# Toilet_Timer.net
KiCad netlist of a schematic drawn in Altium Designer
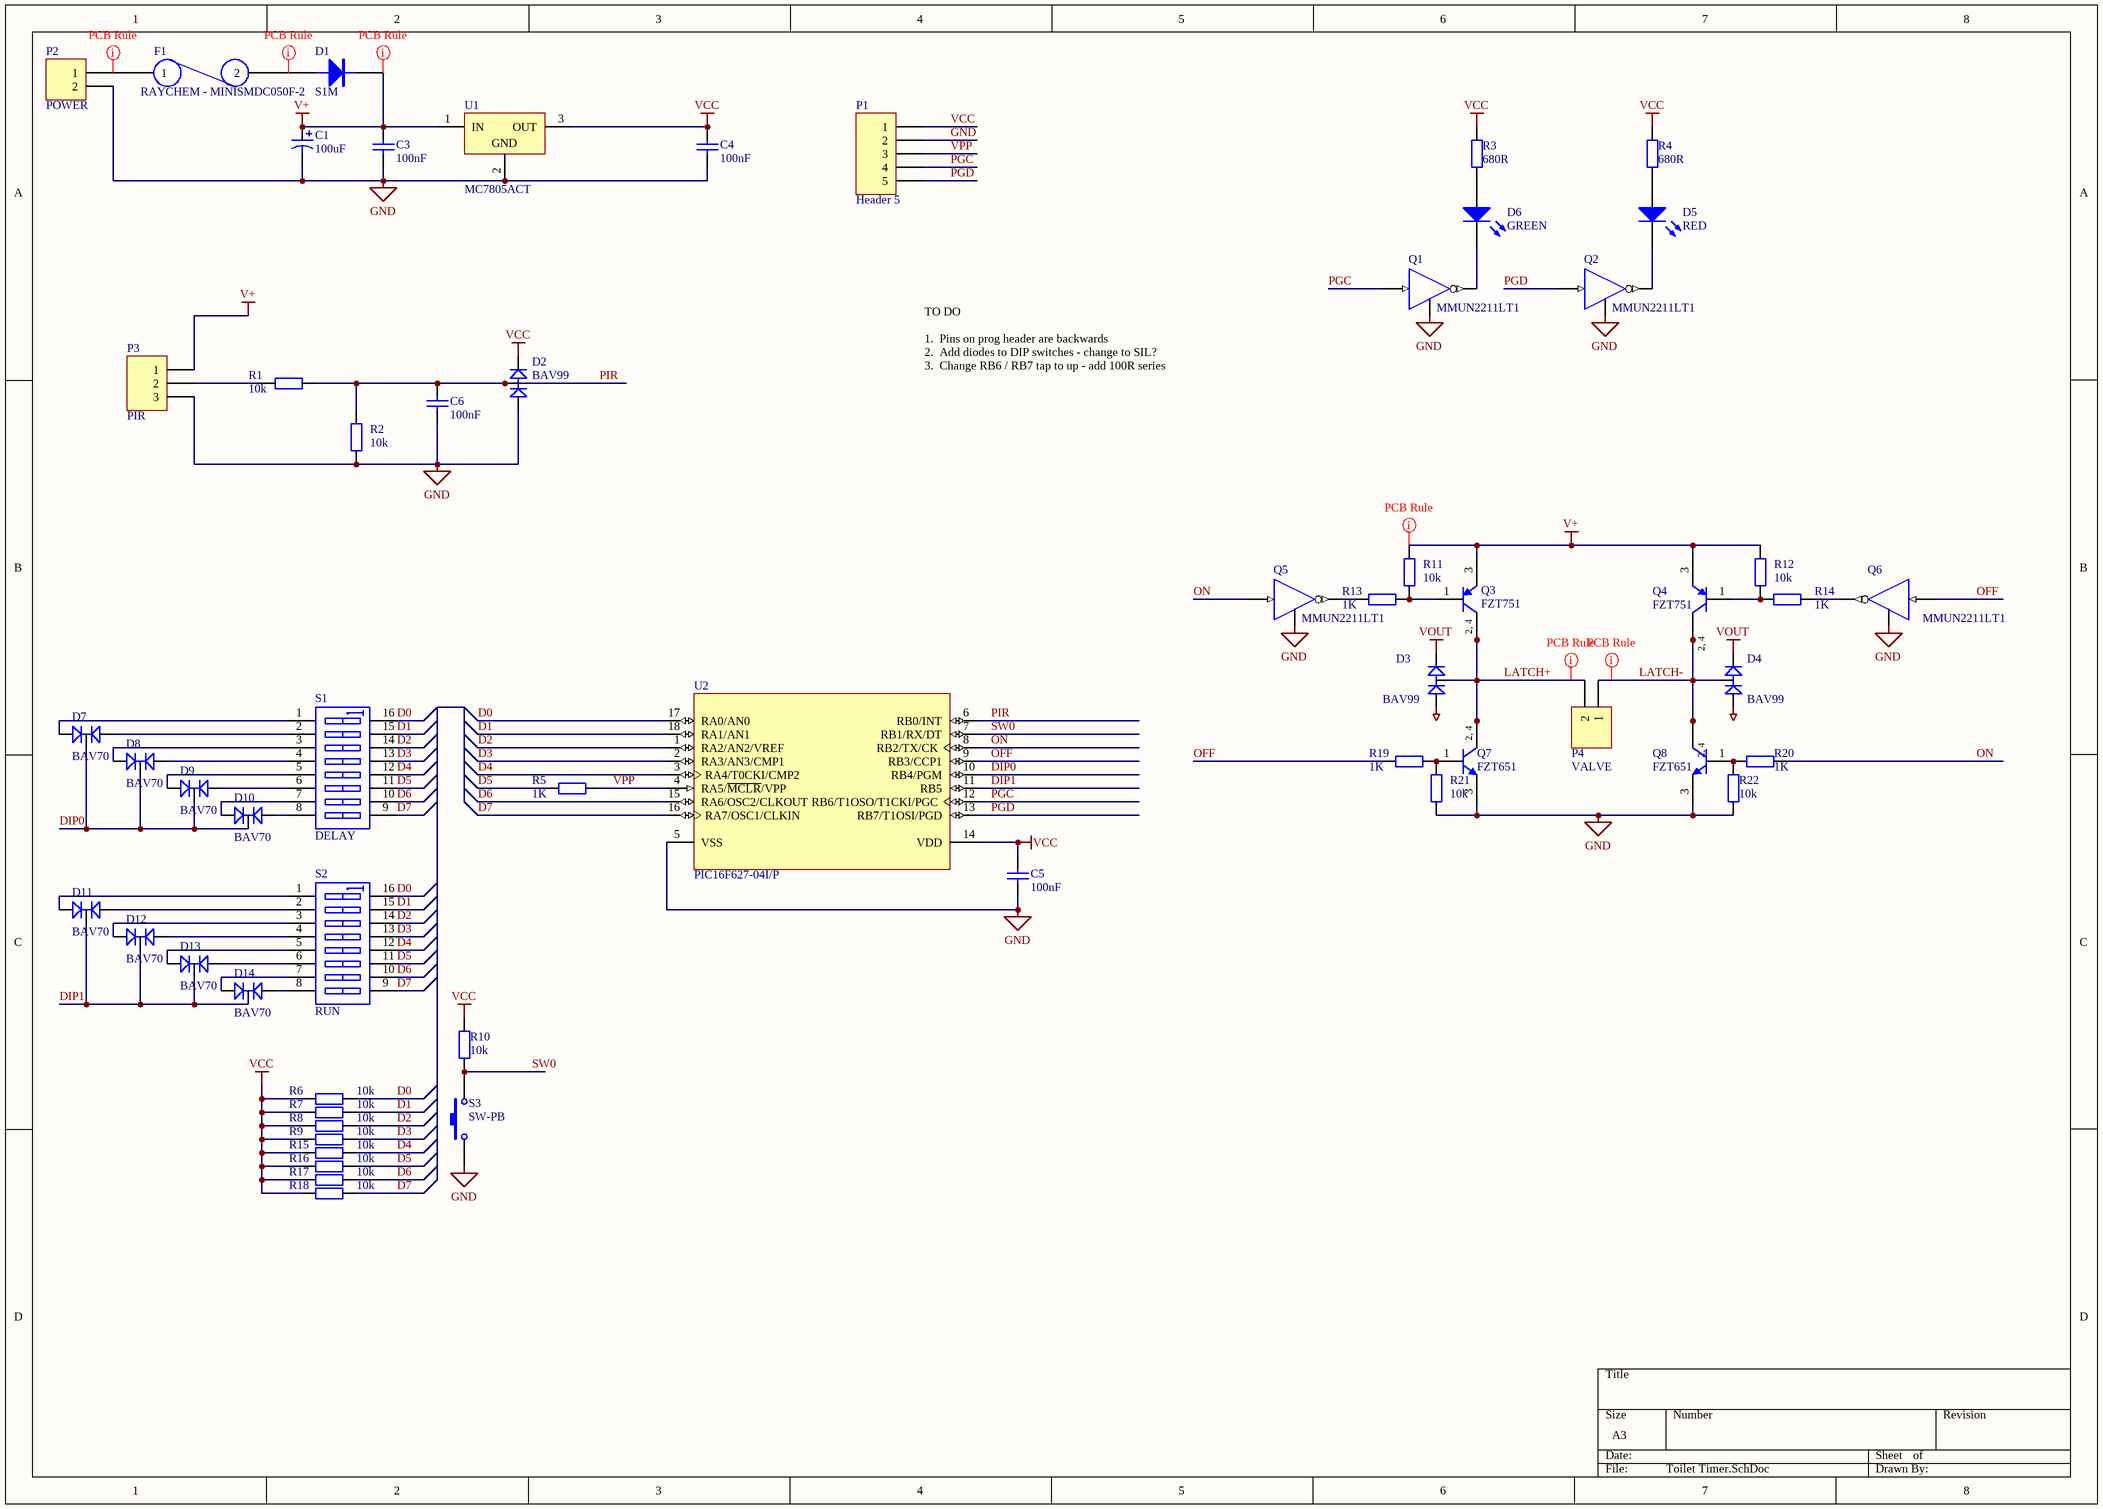
[diagram p0: Toilet Timer.SchDoc]

(export (version "E")
  (design (tool "Eeschema 10.0.6"))
  (components
    (comp (ref "C1")
      (value "100uF")
      (footprint "CAP, SMD E CASE")
      (description "Polarized Capacitor (Radial)")
      (fields (field (name "MOUSER PART NO.") "647-UVR1H101MPD1TA") (field (name "Comment") "Cap Pol1"))
      (libsource (lib "Miscellaneous Devices") (part "Cap Pol1"))
    )
    (comp (ref "C3")
      (value "100nF")
      (footprint "CAP(3D) - 0805")
      (description "Capacitor")
      (fields (field (name "MOUSER PART NO.") "K104Z15Y5VE5TH5") (field (name "Comment") "Cap"))
      (libsource (lib "Miscellaneous Devices") (part "Cap"))
    )
    (comp (ref "C4")
      (value "100nF")
      (footprint "CAP(3D) - 0805")
      (description "Capacitor")
      (fields (field (name "MOUSER PART NO.") "K104Z15Y5VE5TH5") (field (name "Comment") "Cap"))
      (libsource (lib "Miscellaneous Devices") (part "Cap"))
    )
    (comp (ref "C5")
      (value "100nF")
      (footprint "CAP(3D) - 0805")
      (description "Capacitor")
      (fields (field (name "MOUSER PART NO.") "K104Z15Y5VE5TH5") (field (name "Comment") "Cap"))
      (libsource (lib "Miscellaneous Devices") (part "Cap"))
    )
    (comp (ref "C6")
      (value "100nF")
      (footprint "CAP(3D) - 0805")
      (description "Capacitor")
      (fields (field (name "MOUSER PART NO.") "K104Z15Y5VE5TH5") (field (name "Comment") "Cap"))
      (libsource (lib "Miscellaneous Devices") (part "Cap"))
    )
    (comp (ref "D1")
      (value "S1M")
      (footprint "DO-214AC")
      (description "DIODE, POWER")
      (fields (field (name "MOUSER PART NO.") "821-S1M") (field (name "FARNELL PART NO.") "9843841"))
      (libsource (lib "401 CCPA") (part "DIODE"))
    )
    (comp (ref "D2")
      (value "BAV99")
      (footprint "SOT23-3L")
      (description "DUAL DIODE, BAV99")
      (fields (field (name "MOUSER PART NO.") "771-BAV99/T3") (field (name "FARNELL PART NO.") "9843612"))
      (libsource (lib "401 CCPA") (part "BAV99"))
    )
    (comp (ref "D3")
      (value "BAV99")
      (footprint "SOT23-3L")
      (description "DUAL DIODE, BAV99")
      (fields (field (name "MOUSER PART NO.") "771-BAV99/T3") (field (name "FARNELL PART NO.") "9843612"))
      (libsource (lib "401 CCPA") (part "BAV99"))
    )
    (comp (ref "D4")
      (value "BAV99")
      (footprint "SOT23-3L")
      (description "DUAL DIODE, BAV99")
      (fields (field (name "MOUSER PART NO.") "771-BAV99/T3") (field (name "FARNELL PART NO.") "9843612"))
      (libsource (lib "401 CCPA") (part "BAV99"))
    )
    (comp (ref "D5")
      (value "RED")
      (footprint "LED(3D) RED - 0805")
      (description "Typical INFRARED GaAs LED")
      (fields (field (name "MOUSER PART NO.") "606-4308H1"))
      (libsource (lib "Miscellaneous Devices") (part "LED0"))
    )
    (comp (ref "D6")
      (value "GREEN")
      (footprint "LED(3D) GREEN - 0805")
      (description "Typical INFRARED GaAs LED")
      (fields (field (name "MOUSER PART NO.") "606-4308H5"))
      (libsource (lib "Miscellaneous Devices") (part "LED0"))
    )
    (comp (ref "D7")
      (value "BAV70")
      (footprint "SOT23-3L")
      (description "DUAL DIODE, BAV99")
      (fields
        (field (name "FARNELL PART NO.") "9843612")
        (field (name "MANUFACTURER") "FAIRCHILD SEMICONDUCTOR")
      )
      (libsource (lib "Toilet Timer") (part "BAV70"))
    )
    (comp (ref "D8")
      (value "BAV70")
      (footprint "SOT23-3L")
      (description "DUAL DIODE, BAV99")
      (fields
        (field (name "FARNELL PART NO.") "9843612")
        (field (name "MANUFACTURER") "FAIRCHILD SEMICONDUCTOR")
      )
      (libsource (lib "Toilet Timer") (part "BAV70"))
    )
    (comp (ref "D9")
      (value "BAV70")
      (footprint "SOT23-3L")
      (description "DUAL DIODE, BAV99")
      (fields
        (field (name "FARNELL PART NO.") "9843612")
        (field (name "MANUFACTURER") "FAIRCHILD SEMICONDUCTOR")
      )
      (libsource (lib "Toilet Timer") (part "BAV70"))
    )
    (comp (ref "D10")
      (value "BAV70")
      (footprint "SOT23-3L")
      (description "DUAL DIODE, BAV99")
      (fields
        (field (name "FARNELL PART NO.") "9843612")
        (field (name "MANUFACTURER") "FAIRCHILD SEMICONDUCTOR")
      )
      (libsource (lib "Toilet Timer") (part "BAV70"))
    )
    (comp (ref "D11")
      (value "BAV70")
      (footprint "SOT23-3L")
      (description "DUAL DIODE, BAV99")
      (fields
        (field (name "FARNELL PART NO.") "9843612")
        (field (name "MANUFACTURER") "FAIRCHILD SEMICONDUCTOR")
      )
      (libsource (lib "Toilet Timer") (part "BAV70"))
    )
    (comp (ref "D12")
      (value "BAV70")
      (footprint "SOT23-3L")
      (description "DUAL DIODE, BAV99")
      (fields
        (field (name "FARNELL PART NO.") "9843612")
        (field (name "MANUFACTURER") "FAIRCHILD SEMICONDUCTOR")
      )
      (libsource (lib "Toilet Timer") (part "BAV70"))
    )
    (comp (ref "D13")
      (value "BAV70")
      (footprint "SOT23-3L")
      (description "DUAL DIODE, BAV99")
      (fields
        (field (name "FARNELL PART NO.") "9843612")
        (field (name "MANUFACTURER") "FAIRCHILD SEMICONDUCTOR")
      )
      (libsource (lib "Toilet Timer") (part "BAV70"))
    )
    (comp (ref "D14")
      (value "BAV70")
      (footprint "SOT23-3L")
      (description "DUAL DIODE, BAV99")
      (fields
        (field (name "FARNELL PART NO.") "9843612")
        (field (name "MANUFACTURER") "FAIRCHILD SEMICONDUCTOR")
      )
      (libsource (lib "Toilet Timer") (part "BAV70"))
    )
    (comp (ref "F1")
      (value "RAYCHEM - MINISMDC050F-2")
      (footprint "miniSMD Polyswitch")
      (fields
        (field (name "MOUSER PART NO.") "650-MINISMDC050F-2")
        (field (name "FARNELL PART NO.") "1175839")
        (field (name "MANUFACTURER") "Tyco Electronics / Raychem")
      )
      (libsource (lib "401 CCPA") (part "POLYSWITCH"))
    )
    (comp (ref "P1")
      (value "Header 5")
      (footprint "TERMINAL-6 POL")
      (description "Header, 5-Pin")
      (fields (field (name "MOUSER PART NO.") "571-6404565"))
      (libsource (lib "Miscellaneous Connectors") (part "Header 5"))
    )
    (comp (ref "P2")
      (value "POWER")
      (footprint "TYCO  1776112-2")
      (description "Header, 2-Pin")
      (fields (field (name "PUBLISHER") "Altium Limited"))
      (libsource (lib "Miscellaneous Connectors") (part "Header 2"))
    )
    (comp (ref "P3")
      (value "PIR")
      (footprint "TYCO  1776112-3")
      (description "Header, 3-Pin")
      (fields (field (name "PUBLISHER") "Altium Limited"))
      (libsource (lib "Miscellaneous Connectors") (part "Header 3"))
    )
    (comp (ref "P4")
      (value "VALVE")
      (footprint "TYCO  1776112-2")
      (description "Header, 2-Pin")
      (fields (field (name "PUBLISHER") "Altium Limited"))
      (libsource (lib "Miscellaneous Connectors") (part "Header 2"))
    )
    (comp (ref "Q1")
      (value "MMUN2211LT1")
      (footprint "SOT23-3L")
      (fields
        (field (name "MOUSER PART NO.") "863-MMUN2211LT1G")
        (field (name "FARNELL PART NO.") "9556648RL")
        (field (name "MANUFACTURER") "ON Semiconductor")
      )
      (libsource (lib "401 CCPA") (part "NPN DIGITAL TRANSISTOR"))
    )
    (comp (ref "Q2")
      (value "MMUN2211LT1")
      (footprint "SOT23-3L")
      (fields
        (field (name "MOUSER PART NO.") "863-MMUN2211LT1G")
        (field (name "FARNELL PART NO.") "9556648RL")
        (field (name "MANUFACTURER") "ON Semiconductor")
      )
      (libsource (lib "401 CCPA") (part "NPN DIGITAL TRANSISTOR"))
    )
    (comp (ref "Q3")
      (value "FZT751")
      (footprint "SOT223")
      (description "SOT223 PNP Silicon Planar High-Performance Transistor")
      (fields (field (name "PUBLISHER") "Altium Limited"))
      (libsource (lib "Zetex Discrete BJT") (part "FZT751"))
    )
    (comp (ref "Q4")
      (value "FZT751")
      (footprint "SOT223")
      (description "SOT223 PNP Silicon Planar High-Performance Transistor")
      (fields (field (name "PUBLISHER") "Altium Limited"))
      (libsource (lib "Zetex Discrete BJT") (part "FZT751"))
    )
    (comp (ref "Q5")
      (value "MMUN2211LT1")
      (footprint "SOT23-3L")
      (fields
        (field (name "MOUSER PART NO.") "863-MMUN2211LT1G")
        (field (name "FARNELL PART NO.") "9556648RL")
        (field (name "MANUFACTURER") "ON Semiconductor")
      )
      (libsource (lib "401 CCPA") (part "NPN DIGITAL TRANSISTOR"))
    )
    (comp (ref "Q6")
      (value "MMUN2211LT1")
      (footprint "SOT23-3L")
      (fields
        (field (name "MOUSER PART NO.") "863-MMUN2211LT1G")
        (field (name "FARNELL PART NO.") "9556648RL")
        (field (name "MANUFACTURER") "ON Semiconductor")
      )
      (libsource (lib "401 CCPA") (part "NPN DIGITAL TRANSISTOR"))
    )
    (comp (ref "Q7")
      (value "FZT651")
      (footprint "SOT223")
      (description "SOT223 NPN Silicon Planar High-Performance Transistor")
      (fields (field (name "PUBLISHER") "Altium Limited"))
      (libsource (lib "Zetex Discrete BJT") (part "FZT651"))
    )
    (comp (ref "Q8")
      (value "FZT651")
      (footprint "SOT223")
      (description "SOT223 NPN Silicon Planar High-Performance Transistor")
      (fields (field (name "PUBLISHER") "Altium Limited"))
      (libsource (lib "Zetex Discrete BJT") (part "FZT651"))
    )
    (comp (ref "R1")
      (value "10k")
      (footprint "RES(3D) - 0805")
      (description "Resistor")
      (fields (field (name "MOUSER PART NO.") "660-MF1/4LCT52R103J") (field (name "Comment") "Res2"))
      (libsource (lib "") (part "Res2_2"))
    )
    (comp (ref "R2")
      (value "10k")
      (footprint "RES(3D) - 0805")
      (description "Resistor")
      (fields (field (name "MOUSER PART NO.") "660-MF1/4LCT52R103J") (field (name "Comment") "Res2"))
      (libsource (lib "") (part "Res2_1"))
    )
    (comp (ref "R3")
      (value "680R")
      (footprint "RES(3D) - 0805")
      (description "Resistor")
      (fields (field (name "MOUSER PART NO.") "660-MF1/4DCT52R6800F") (field (name "Comment") "Res2"))
      (libsource (lib "") (part "Res2_1"))
    )
    (comp (ref "R4")
      (value "680R")
      (footprint "RES(3D) - 0805")
      (description "Resistor")
      (fields (field (name "MOUSER PART NO.") "660-MF1/4DCT52R6800F") (field (name "Comment") "Res2"))
      (libsource (lib "") (part "Res2_1"))
    )
    (comp (ref "R5")
      (value "1K")
      (footprint "RES(3D) - 0805")
      (description "Resistor")
      (fields (field (name "MOUSER PART NO.") "660-MF1/4DCT52R1102F") (field (name "Comment") "Res2"))
      (libsource (lib "") (part "Res2_2"))
    )
    (comp (ref "R6")
      (value "10k")
      (footprint "RES(3D) - 0805")
      (description "Resistor")
      (fields (field (name "MOUSER PART NO.") "660-MF1/4LCT52R103J") (field (name "Comment") "Res2"))
      (libsource (lib "") (part "Res2_3"))
    )
    (comp (ref "R7")
      (value "10k")
      (footprint "RES(3D) - 0805")
      (description "Resistor")
      (fields (field (name "MOUSER PART NO.") "660-MF1/4LCT52R103J") (field (name "Comment") "Res2"))
      (libsource (lib "") (part "Res2_3"))
    )
    (comp (ref "R8")
      (value "10k")
      (footprint "RES(3D) - 0805")
      (description "Resistor")
      (fields (field (name "MOUSER PART NO.") "660-MF1/4LCT52R103J") (field (name "Comment") "Res2"))
      (libsource (lib "") (part "Res2_3"))
    )
    (comp (ref "R9")
      (value "10k")
      (footprint "RES(3D) - 0805")
      (description "Resistor")
      (fields (field (name "MOUSER PART NO.") "660-MF1/4LCT52R103J") (field (name "Comment") "Res2"))
      (libsource (lib "") (part "Res2_3"))
    )
    (comp (ref "R10")
      (value "10k")
      (footprint "RES(3D) - 0805")
      (description "Resistor")
      (fields (field (name "MOUSER PART NO.") "660-MF1/4LCT52R103J") (field (name "Comment") "Res2"))
      (libsource (lib "Miscellaneous Devices") (part "Res2"))
    )
    (comp (ref "R11")
      (value "10k")
      (footprint "RES(3D) - 0805")
      (description "Resistor")
      (fields (field (name "MOUSER PART NO.") "660-MF1/4LCT52R103J") (field (name "Comment") "Res2"))
      (libsource (lib "") (part "Res2_1"))
    )
    (comp (ref "R12")
      (value "10k")
      (footprint "RES(3D) - 0805")
      (description "Resistor")
      (fields (field (name "MOUSER PART NO.") "660-MF1/4LCT52R103J") (field (name "Comment") "Res2"))
      (libsource (lib "") (part "Res2_1"))
    )
    (comp (ref "R13")
      (value "1K")
      (footprint "RES(3D) - 0805")
      (description "Resistor")
      (fields (field (name "MOUSER PART NO.") "660-MF1/4DCT52R1102F") (field (name "Comment") "Res2"))
      (libsource (lib "") (part "Res2_2"))
    )
    (comp (ref "R14")
      (value "1K")
      (footprint "RES(3D) - 0805")
      (description "Resistor")
      (fields (field (name "MOUSER PART NO.") "660-MF1/4DCT52R1102F") (field (name "Comment") "Res2"))
      (libsource (lib "Miscellaneous Devices") (part "Res2"))
    )
    (comp (ref "R15")
      (value "10k")
      (footprint "RES(3D) - 0805")
      (description "Resistor")
      (fields (field (name "MOUSER PART NO.") "660-MF1/4LCT52R103J") (field (name "Comment") "Res2"))
      (libsource (lib "") (part "Res2_3"))
    )
    (comp (ref "R16")
      (value "10k")
      (footprint "RES(3D) - 0805")
      (description "Resistor")
      (fields (field (name "MOUSER PART NO.") "660-MF1/4LCT52R103J") (field (name "Comment") "Res2"))
      (libsource (lib "") (part "Res2_3"))
    )
    (comp (ref "R17")
      (value "10k")
      (footprint "RES(3D) - 0805")
      (description "Resistor")
      (fields (field (name "MOUSER PART NO.") "660-MF1/4LCT52R103J") (field (name "Comment") "Res2"))
      (libsource (lib "") (part "Res2_3"))
    )
    (comp (ref "R18")
      (value "10k")
      (footprint "RES(3D) - 0805")
      (description "Resistor")
      (fields (field (name "MOUSER PART NO.") "660-MF1/4LCT52R103J") (field (name "Comment") "Res2"))
      (libsource (lib "") (part "Res2_3"))
    )
    (comp (ref "R19")
      (value "1K")
      (footprint "RES(3D) - 0805")
      (description "Resistor")
      (fields (field (name "MOUSER PART NO.") "660-MF1/4DCT52R1102F") (field (name "Comment") "Res2"))
      (libsource (lib "") (part "Res2_2"))
    )
    (comp (ref "R20")
      (value "1K")
      (footprint "RES(3D) - 0805")
      (description "Resistor")
      (fields (field (name "MOUSER PART NO.") "660-MF1/4DCT52R1102F") (field (name "Comment") "Res2"))
      (libsource (lib "Miscellaneous Devices") (part "Res2"))
    )
    (comp (ref "R21")
      (value "10k")
      (footprint "RES(3D) - 0805")
      (description "Resistor")
      (fields (field (name "MOUSER PART NO.") "660-MF1/4LCT52R103J") (field (name "Comment") "Res2"))
      (libsource (lib "") (part "Res2_1"))
    )
    (comp (ref "R22")
      (value "10k")
      (footprint "RES(3D) - 0805")
      (description "Resistor")
      (fields (field (name "MOUSER PART NO.") "660-MF1/4LCT52R103J") (field (name "Comment") "Res2"))
      (libsource (lib "") (part "Res2_2"))
    )
    (comp (ref "S1")
      (value "DELAY")
      (footprint "S-DIP-16")
      (description "DIP Switch, 8 Position, SPST")
      (fields (field (name "MOUSER PART NO.") "774-2068"))
      (libsource (lib "Miscellaneous Devices") (part "SW DIP-8"))
    )
    (comp (ref "S2")
      (value "RUN")
      (footprint "S-DIP-16")
      (description "DIP Switch, 8 Position, SPST")
      (fields (field (name "MOUSER PART NO.") "774-2068"))
      (libsource (lib "Miscellaneous Devices") (part "SW DIP-8"))
    )
    (comp (ref "S3")
      (value "SW-PB")
      (footprint "TACT 6MM")
      (description "Switch")
      (fields (field (name "MOUSER PART NO.") "642-MJTP1230"))
      (libsource (lib "Miscellaneous Devices") (part "SW-PB"))
    )
    (comp (ref "U1")
      (value "MC7805ACT")
      (footprint "7805 - DPAK")
      (description "3-Terminal Positive Fixed Voltage Regulator")
      (fields (field (name "MOUSER PART NO.") "512-LM7805ACT"))
      (libsource (lib "Motorola Power Mgt Voltage Regulator") (part "MC7805ACT"))
    )
    (comp (ref "U2")
      (value "PIC16F627-04I/P")
      (footprint "SOIC-18")
      (fields (field (name "MOUSER PART NO.") "579-PIC16F627A-I/P"))
      (libsource (lib "Microchip Microcontroller 8-Bit PIC16F") (part "PIC16F627-04I/P"))
    )
  )
  (nets
    (net (code "1") (name "/D0") (class "Default")
      (node (ref "R6") (pin "1") (pinfunction "1_1") (pintype "passive"))
      (node (ref "S1") (pin "16") (pinfunction "B1_16") (pintype "passive"))
      (node (ref "S2") (pin "16") (pinfunction "B1_16") (pintype "passive"))
      (node (ref "U2") (pin "17") (pinfunction "RA0/AN0_17") (pintype "bidirectional"))
    )
    (net (code "2") (name "/D1") (class "Default")
      (node (ref "R7") (pin "1") (pinfunction "1_1") (pintype "passive"))
      (node (ref "S1") (pin "15") (pinfunction "B2_15") (pintype "passive"))
      (node (ref "S2") (pin "15") (pinfunction "B2_15") (pintype "passive"))
      (node (ref "U2") (pin "18") (pinfunction "RA1/AN1_18") (pintype "bidirectional"))
    )
    (net (code "3") (name "/D2") (class "Default")
      (node (ref "R8") (pin "1") (pinfunction "1_1") (pintype "passive"))
      (node (ref "S1") (pin "14") (pinfunction "B3_14") (pintype "passive"))
      (node (ref "S2") (pin "14") (pinfunction "B3_14") (pintype "passive"))
      (node (ref "U2") (pin "1") (pinfunction "RA2/AN2/VREF_1") (pintype "bidirectional"))
    )
    (net (code "4") (name "/D3") (class "Default")
      (node (ref "R9") (pin "1") (pinfunction "1_1") (pintype "passive"))
      (node (ref "S1") (pin "13") (pinfunction "B4_13") (pintype "passive"))
      (node (ref "S2") (pin "13") (pinfunction "B4_13") (pintype "passive"))
      (node (ref "U2") (pin "2") (pinfunction "RA3/AN3/CMP1_2") (pintype "bidirectional"))
    )
    (net (code "5") (name "/D4") (class "Default")
      (node (ref "R15") (pin "1") (pinfunction "1_1") (pintype "passive"))
      (node (ref "S1") (pin "12") (pinfunction "B5_12") (pintype "passive"))
      (node (ref "S2") (pin "12") (pinfunction "B5_12") (pintype "passive"))
      (node (ref "U2") (pin "3") (pinfunction "RA4/T0CKI/CMP2_3") (pintype "bidirectional"))
    )
    (net (code "6") (name "/D5") (class "Default")
      (node (ref "R16") (pin "1") (pinfunction "1_1") (pintype "passive"))
      (node (ref "R5") (pin "1") (pinfunction "1_1") (pintype "passive"))
      (node (ref "S1") (pin "11") (pinfunction "B6_11") (pintype "passive"))
      (node (ref "S2") (pin "11") (pinfunction "B6_11") (pintype "passive"))
    )
    (net (code "7") (name "/D6") (class "Default")
      (node (ref "R17") (pin "1") (pinfunction "1_1") (pintype "passive"))
      (node (ref "S1") (pin "10") (pinfunction "B7_10") (pintype "passive"))
      (node (ref "S2") (pin "10") (pinfunction "B7_10") (pintype "passive"))
      (node (ref "U2") (pin "15") (pinfunction "RA6/OSC2/CLKOUT_15") (pintype "bidirectional"))
    )
    (net (code "8") (name "/D7") (class "Default")
      (node (ref "R18") (pin "1") (pinfunction "1_1") (pintype "passive"))
      (node (ref "S1") (pin "9") (pinfunction "B8_9") (pintype "passive"))
      (node (ref "S2") (pin "9") (pinfunction "B8_9") (pintype "passive"))
      (node (ref "U2") (pin "16") (pinfunction "RA7/OSC1/CLKIN_16") (pintype "bidirectional"))
    )
    (net (code "9") (name "/DIP0") (class "Default")
      (node (ref "D10") (pin "3") (pinfunction "C_3") (pintype "passive"))
      (node (ref "D7") (pin "3") (pinfunction "C_3") (pintype "passive"))
      (node (ref "D8") (pin "3") (pinfunction "C_3") (pintype "passive"))
      (node (ref "D9") (pin "3") (pinfunction "C_3") (pintype "passive"))
      (node (ref "U2") (pin "10") (pinfunction "RB4/PGM_10") (pintype "bidirectional"))
    )
    (net (code "10") (name "/DIP1") (class "Default")
      (node (ref "D11") (pin "3") (pinfunction "C_3") (pintype "passive"))
      (node (ref "D12") (pin "3") (pinfunction "C_3") (pintype "passive"))
      (node (ref "D13") (pin "3") (pinfunction "C_3") (pintype "passive"))
      (node (ref "D14") (pin "3") (pinfunction "C_3") (pintype "passive"))
      (node (ref "U2") (pin "11") (pinfunction "RB5_11") (pintype "bidirectional"))
    )
    (net (code "11") (name "/LATCH+") (class "Default")
      (node (ref "D3") (pin "3") (pinfunction "C1/A2_3") (pintype "passive"))
      (node (ref "P4") (pin "2") (pinfunction "2_2") (pintype "passive"))
      (node (ref "Q3") (pin "2") (pinfunction "C_2") (pintype "passive"))
      (node (ref "Q3") (pin "4") (pinfunction "C_4") (pintype "passive"))
      (node (ref "Q7") (pin "2") (pinfunction "C_2") (pintype "passive"))
      (node (ref "Q7") (pin "4") (pinfunction "C_4") (pintype "passive"))
    )
    (net (code "12") (name "/LATCH-") (class "Default")
      (node (ref "D4") (pin "3") (pinfunction "C1/A2_3") (pintype "passive"))
      (node (ref "P4") (pin "1") (pinfunction "1_1") (pintype "passive"))
      (node (ref "Q4") (pin "2") (pinfunction "C_2") (pintype "passive"))
      (node (ref "Q4") (pin "4") (pinfunction "C_4") (pintype "passive"))
      (node (ref "Q8") (pin "2") (pinfunction "C_2") (pintype "passive"))
      (node (ref "Q8") (pin "4") (pinfunction "C_4") (pintype "passive"))
    )
    (net (code "13") (name "/OFF") (class "Default")
      (node (ref "Q6") (pin "1") (pinfunction "B_1") (pintype "input"))
      (node (ref "R19") (pin "1") (pinfunction "1_1") (pintype "passive"))
      (node (ref "U2") (pin "9") (pinfunction "RB3/CCP1_9") (pintype "bidirectional"))
    )
    (net (code "14") (name "/ON") (class "Default")
      (node (ref "Q5") (pin "1") (pinfunction "B_1") (pintype "input"))
      (node (ref "R20") (pin "1") (pinfunction "1_1") (pintype "passive"))
      (node (ref "U2") (pin "8") (pinfunction "RB2/TX/CK_8") (pintype "bidirectional"))
    )
    (net (code "15") (name "/PGC") (class "Default")
      (node (ref "P1") (pin "4") (pinfunction "4_4") (pintype "passive"))
      (node (ref "Q1") (pin "1") (pinfunction "B_1") (pintype "input"))
      (node (ref "U2") (pin "12") (pinfunction "RB6/T1OSO/T1CKI/PGC_12") (pintype "bidirectional"))
    )
    (net (code "16") (name "/PGD") (class "Default")
      (node (ref "P1") (pin "5") (pinfunction "5_5") (pintype "passive"))
      (node (ref "Q2") (pin "1") (pinfunction "B_1") (pintype "input"))
      (node (ref "U2") (pin "13") (pinfunction "RB7/T1OSI/PGD_13") (pintype "bidirectional"))
    )
    (net (code "17") (name "/PIR") (class "Default")
      (node (ref "C6") (pin "2") (pinfunction "2_2") (pintype "passive"))
      (node (ref "D2") (pin "3") (pinfunction "C1/A2_3") (pintype "passive"))
      (node (ref "R1") (pin "2") (pinfunction "2_2") (pintype "passive"))
      (node (ref "R2") (pin "2") (pinfunction "2_2") (pintype "passive"))
      (node (ref "U2") (pin "6") (pinfunction "RB0/INT_6") (pintype "bidirectional"))
    )
    (net (code "18") (name "/SW0") (class "Default")
      (node (ref "R10") (pin "2") (pinfunction "2_2") (pintype "passive"))
      (node (ref "S3") (pin "2") (pinfunction "2_2") (pintype "passive"))
      (node (ref "U2") (pin "7") (pinfunction "RB1/RX/DT_7") (pintype "bidirectional"))
    )
    (net (code "19") (name "/VPP") (class "Default")
      (node (ref "P1") (pin "3") (pinfunction "3_3") (pintype "passive"))
      (node (ref "R5") (pin "2") (pinfunction "2_2") (pintype "passive"))
      (node (ref "U2") (pin "4") (pinfunction "RA5/~{MCLR}/VPP_4") (pintype "input"))
    )
    (net (code "20") (name "GND") (class "Default")
      (node (ref "C1") (pin "2") (pinfunction "2_2") (pintype "passive"))
      (node (ref "C3") (pin "1") (pinfunction "1_1") (pintype "passive"))
      (node (ref "C4") (pin "1") (pinfunction "1_1") (pintype "passive"))
      (node (ref "C5") (pin "1") (pinfunction "1_1") (pintype "passive"))
      (node (ref "C6") (pin "1") (pinfunction "1_1") (pintype "passive"))
      (node (ref "D2") (pin "1") (pinfunction "A1_1") (pintype "passive"))
      (node (ref "D3") (pin "1") (pinfunction "A1_1") (pintype "passive"))
      (node (ref "D4") (pin "1") (pinfunction "A1_1") (pintype "passive"))
      (node (ref "P1") (pin "2") (pinfunction "2_2") (pintype "passive"))
      (node (ref "P2") (pin "2") (pinfunction "2_2") (pintype "passive"))
      (node (ref "P3") (pin "3") (pinfunction "3_3") (pintype "passive"))
      (node (ref "Q1") (pin "2") (pinfunction "E_2") (pintype "passive"))
      (node (ref "Q2") (pin "2") (pinfunction "E_2") (pintype "passive"))
      (node (ref "Q5") (pin "2") (pinfunction "E_2") (pintype "passive"))
      (node (ref "Q6") (pin "2") (pinfunction "E_2") (pintype "passive"))
      (node (ref "Q7") (pin "3") (pinfunction "E_3") (pintype "passive"))
      (node (ref "Q8") (pin "3") (pinfunction "E_3") (pintype "passive"))
      (node (ref "R2") (pin "1") (pinfunction "1_1") (pintype "passive"))
      (node (ref "R21") (pin "1") (pinfunction "1_1") (pintype "passive"))
      (node (ref "R22") (pin "1") (pinfunction "1_1") (pintype "passive"))
      (node (ref "S3") (pin "1") (pinfunction "1_1") (pintype "passive"))
      (node (ref "U1") (pin "2") (pinfunction "GND_2") (pintype "power_in"))
      (node (ref "U2") (pin "5") (pinfunction "VSS_5") (pintype "power_in"))
    )
    (net (code "21") (name "Net-(D1-A)") (class "Default")
      (node (ref "D1") (pin "1") (pinfunction "A_1") (pintype "passive"))
      (node (ref "F1") (pin "2") (pinfunction "2_2") (pintype "passive"))
    )
    (net (code "22") (name "Net-(D5-A)") (class "Default")
      (node (ref "D5") (pin "1") (pinfunction "A_1") (pintype "passive"))
      (node (ref "R4") (pin "1") (pinfunction "1_1") (pintype "passive"))
    )
    (net (code "23") (name "Net-(D5-K)") (class "Default")
      (node (ref "D5") (pin "2") (pinfunction "K_2") (pintype "passive"))
      (node (ref "Q2") (pin "3") (pinfunction "C_3") (pintype "output"))
    )
    (net (code "24") (name "Net-(D6-A)") (class "Default")
      (node (ref "D6") (pin "1") (pinfunction "A_1") (pintype "passive"))
      (node (ref "R3") (pin "1") (pinfunction "1_1") (pintype "passive"))
    )
    (net (code "25") (name "Net-(D6-K)") (class "Default")
      (node (ref "D6") (pin "2") (pinfunction "K_2") (pintype "passive"))
      (node (ref "Q1") (pin "3") (pinfunction "C_3") (pintype "output"))
    )
    (net (code "26") (name "Net-(D7-A1)") (class "Default")
      (node (ref "D7") (pin "1") (pinfunction "A1_1") (pintype "passive"))
      (node (ref "S1") (pin "2") (pinfunction "A2_2") (pintype "passive"))
    )
    (net (code "27") (name "Net-(D7-A2)") (class "Default")
      (node (ref "D7") (pin "2") (pinfunction "A2_2") (pintype "passive"))
      (node (ref "S1") (pin "1") (pinfunction "A1_1") (pintype "passive"))
    )
    (net (code "28") (name "Net-(D8-A1)") (class "Default")
      (node (ref "D8") (pin "1") (pinfunction "A1_1") (pintype "passive"))
      (node (ref "S1") (pin "4") (pinfunction "A4_4") (pintype "passive"))
    )
    (net (code "29") (name "Net-(D8-A2)") (class "Default")
      (node (ref "D8") (pin "2") (pinfunction "A2_2") (pintype "passive"))
      (node (ref "S1") (pin "3") (pinfunction "A3_3") (pintype "passive"))
    )
    (net (code "30") (name "Net-(D9-A1)") (class "Default")
      (node (ref "D9") (pin "1") (pinfunction "A1_1") (pintype "passive"))
      (node (ref "S1") (pin "6") (pinfunction "A6_6") (pintype "passive"))
    )
    (net (code "31") (name "Net-(D9-A2)") (class "Default")
      (node (ref "D9") (pin "2") (pinfunction "A2_2") (pintype "passive"))
      (node (ref "S1") (pin "5") (pinfunction "A5_5") (pintype "passive"))
    )
    (net (code "32") (name "Net-(D10-A1)") (class "Default")
      (node (ref "D10") (pin "1") (pinfunction "A1_1") (pintype "passive"))
      (node (ref "S1") (pin "8") (pinfunction "A8_8") (pintype "passive"))
    )
    (net (code "33") (name "Net-(D10-A2)") (class "Default")
      (node (ref "D10") (pin "2") (pinfunction "A2_2") (pintype "passive"))
      (node (ref "S1") (pin "7") (pinfunction "A7_7") (pintype "passive"))
    )
    (net (code "34") (name "Net-(D11-A1)") (class "Default")
      (node (ref "D11") (pin "1") (pinfunction "A1_1") (pintype "passive"))
      (node (ref "S2") (pin "2") (pinfunction "A2_2") (pintype "passive"))
    )
    (net (code "35") (name "Net-(D11-A2)") (class "Default")
      (node (ref "D11") (pin "2") (pinfunction "A2_2") (pintype "passive"))
      (node (ref "S2") (pin "1") (pinfunction "A1_1") (pintype "passive"))
    )
    (net (code "36") (name "Net-(D12-A1)") (class "Default")
      (node (ref "D12") (pin "1") (pinfunction "A1_1") (pintype "passive"))
      (node (ref "S2") (pin "4") (pinfunction "A4_4") (pintype "passive"))
    )
    (net (code "37") (name "Net-(D12-A2)") (class "Default")
      (node (ref "D12") (pin "2") (pinfunction "A2_2") (pintype "passive"))
      (node (ref "S2") (pin "3") (pinfunction "A3_3") (pintype "passive"))
    )
    (net (code "38") (name "Net-(D13-A1)") (class "Default")
      (node (ref "D13") (pin "1") (pinfunction "A1_1") (pintype "passive"))
      (node (ref "S2") (pin "6") (pinfunction "A6_6") (pintype "passive"))
    )
    (net (code "39") (name "Net-(D13-A2)") (class "Default")
      (node (ref "D13") (pin "2") (pinfunction "A2_2") (pintype "passive"))
      (node (ref "S2") (pin "5") (pinfunction "A5_5") (pintype "passive"))
    )
    (net (code "40") (name "Net-(D14-A1)") (class "Default")
      (node (ref "D14") (pin "1") (pinfunction "A1_1") (pintype "passive"))
      (node (ref "S2") (pin "8") (pinfunction "A8_8") (pintype "passive"))
    )
    (net (code "41") (name "Net-(D14-A2)") (class "Default")
      (node (ref "D14") (pin "2") (pinfunction "A2_2") (pintype "passive"))
      (node (ref "S2") (pin "7") (pinfunction "A7_7") (pintype "passive"))
    )
    (net (code "42") (name "Net-(F1-Pad1)") (class "Default")
      (node (ref "F1") (pin "1") (pinfunction "1_1") (pintype "passive"))
      (node (ref "P2") (pin "1") (pinfunction "1_1") (pintype "passive"))
    )
    (net (code "43") (name "Net-(P3-Pad2)") (class "Default")
      (node (ref "P3") (pin "2") (pinfunction "2_2") (pintype "passive"))
      (node (ref "R1") (pin "1") (pinfunction "1_1") (pintype "passive"))
    )
    (net (code "44") (name "Net-(Q3-B)") (class "Default")
      (node (ref "Q3") (pin "1") (pinfunction "B_1") (pintype "passive"))
      (node (ref "R11") (pin "1") (pinfunction "1_1") (pintype "passive"))
      (node (ref "R13") (pin "2") (pinfunction "2_2") (pintype "passive"))
    )
    (net (code "45") (name "Net-(Q4-B)") (class "Default")
      (node (ref "Q4") (pin "1") (pinfunction "B_1") (pintype "passive"))
      (node (ref "R12") (pin "1") (pinfunction "1_1") (pintype "passive"))
      (node (ref "R14") (pin "2") (pinfunction "2_2") (pintype "passive"))
    )
    (net (code "46") (name "Net-(Q5-C)") (class "Default")
      (node (ref "Q5") (pin "3") (pinfunction "C_3") (pintype "output"))
      (node (ref "R13") (pin "1") (pinfunction "1_1") (pintype "passive"))
    )
    (net (code "47") (name "Net-(Q6-C)") (class "Default")
      (node (ref "Q6") (pin "3") (pinfunction "C_3") (pintype "output"))
      (node (ref "R14") (pin "1") (pinfunction "1_1") (pintype "passive"))
    )
    (net (code "48") (name "Net-(Q7-B)") (class "Default")
      (node (ref "Q7") (pin "1") (pinfunction "B_1") (pintype "passive"))
      (node (ref "R19") (pin "2") (pinfunction "2_2") (pintype "passive"))
      (node (ref "R21") (pin "2") (pinfunction "2_2") (pintype "passive"))
    )
    (net (code "49") (name "Net-(Q8-B)") (class "Default")
      (node (ref "Q8") (pin "1") (pinfunction "B_1") (pintype "passive"))
      (node (ref "R20") (pin "2") (pinfunction "2_2") (pintype "passive"))
      (node (ref "R22") (pin "2") (pinfunction "2_2") (pintype "passive"))
    )
    (net (code "50") (name "V+") (class "Default")
      (node (ref "C1") (pin "1") (pinfunction "1_1") (pintype "passive"))
      (node (ref "C3") (pin "2") (pinfunction "2_2") (pintype "passive"))
      (node (ref "D1") (pin "2") (pinfunction "K_2") (pintype "passive"))
      (node (ref "P3") (pin "1") (pinfunction "1_1") (pintype "passive"))
      (node (ref "Q3") (pin "3") (pinfunction "E_3") (pintype "passive"))
      (node (ref "Q4") (pin "3") (pinfunction "E_3") (pintype "passive"))
      (node (ref "R11") (pin "2") (pinfunction "2_2") (pintype "passive"))
      (node (ref "R12") (pin "2") (pinfunction "2_2") (pintype "passive"))
      (node (ref "U1") (pin "1") (pinfunction "IN_1") (pintype "power_in"))
    )
    (net (code "51") (name "VCC") (class "Default")
      (node (ref "C4") (pin "2") (pinfunction "2_2") (pintype "passive"))
      (node (ref "C5") (pin "2") (pinfunction "2_2") (pintype "passive"))
      (node (ref "D2") (pin "2") (pinfunction "C2_2") (pintype "passive"))
      (node (ref "P1") (pin "1") (pinfunction "1_1") (pintype "passive"))
      (node (ref "R10") (pin "1") (pinfunction "1_1") (pintype "passive"))
      (node (ref "R15") (pin "2") (pinfunction "2_2") (pintype "passive"))
      (node (ref "R16") (pin "2") (pinfunction "2_2") (pintype "passive"))
      (node (ref "R17") (pin "2") (pinfunction "2_2") (pintype "passive"))
      (node (ref "R18") (pin "2") (pinfunction "2_2") (pintype "passive"))
      (node (ref "R3") (pin "2") (pinfunction "2_2") (pintype "passive"))
      (node (ref "R4") (pin "2") (pinfunction "2_2") (pintype "passive"))
      (node (ref "R6") (pin "2") (pinfunction "2_2") (pintype "passive"))
      (node (ref "R7") (pin "2") (pinfunction "2_2") (pintype "passive"))
      (node (ref "R8") (pin "2") (pinfunction "2_2") (pintype "passive"))
      (node (ref "R9") (pin "2") (pinfunction "2_2") (pintype "passive"))
      (node (ref "U1") (pin "3") (pinfunction "OUT_3") (pintype "power_in"))
      (node (ref "U2") (pin "14") (pinfunction "VDD_14") (pintype "power_in"))
    )
    (net (code "52") (name "VOUT") (class "Default")
      (node (ref "D3") (pin "2") (pinfunction "C2_2") (pintype "passive"))
      (node (ref "D4") (pin "2") (pinfunction "C2_2") (pintype "passive"))
    )
  )
)
